# pots.net
KiCad netlist of a schematic drawn in EAGLE
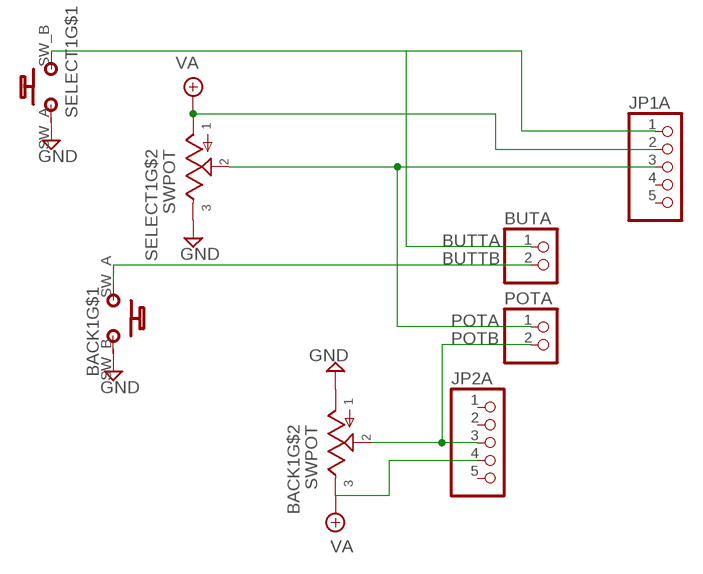
[diagram p0: schematic, sheet 1]

(export (version "E")
  (design (tool "Eeschema 10.0.6"))
  (components
    (comp (ref "BACK1")
      (value "SWPOT")
      (footprint "eagle-import:SWPOT")
      (libsource (lib "eagle-import") (part "SWPOT"))
    )
    (comp (ref "BUTA")
      (value "PINHD-1X2")
      (footprint "eagle-import:1X02")
      (libsource (lib "eagle-import") (part "PINHD-1X2"))
    )
    (comp (ref "JP1A")
      (value "PINHD-1X5")
      (footprint "eagle-import:1X05")
      (libsource (lib "eagle-import") (part "PINHD-1X5"))
    )
    (comp (ref "JP2A")
      (value "PINHD-1X5")
      (footprint "eagle-import:1X05")
      (libsource (lib "eagle-import") (part "PINHD-1X5"))
    )
    (comp (ref "POTA")
      (value "PINHD-1X2")
      (footprint "eagle-import:1X02")
      (libsource (lib "eagle-import") (part "PINHD-1X2"))
    )
    (comp (ref "SELECT1")
      (value "SWPOT")
      (footprint "eagle-import:SWPOT")
      (libsource (lib "eagle-import") (part "SWPOT"))
    )
  )
  (nets
    (net (code "1") (name "/BUTTA") (class "Default")
      (node (ref "BUTA") (pin "1") (pinfunction "1_1") (pintype "passive"))
      (node (ref "JP1A") (pin "1") (pinfunction "1_1") (pintype "passive"))
      (node (ref "SELECT1") (pin "SW_B") (pinfunction "B_B_SW_B") (pintype "passive"))
    )
    (net (code "2") (name "/BUTTB") (class "Default")
      (node (ref "BACK1") (pin "SW_A") (pinfunction "B_A_SW_A") (pintype "passive"))
      (node (ref "BUTA") (pin "2") (pinfunction "2_2") (pintype "passive"))
    )
    (net (code "3") (name "/POTA") (class "Default")
      (node (ref "JP1A") (pin "3") (pinfunction "3_3") (pintype "passive"))
      (node (ref "POTA") (pin "1") (pinfunction "1_1") (pintype "passive"))
      (node (ref "SELECT1") (pin "POT_W") (pinfunction "POT_W_POT_W") (pintype "passive"))
    )
    (net (code "4") (name "/POTB") (class "Default")
      (node (ref "BACK1") (pin "POT_W") (pinfunction "POT_W_POT_W") (pintype "passive"))
      (node (ref "JP2A") (pin "3") (pinfunction "3_3") (pintype "passive"))
      (node (ref "POTA") (pin "2") (pinfunction "2_2") (pintype "passive"))
    )
    (net (code "5") (name "GND") (class "Default")
      (node (ref "BACK1") (pin "POT_B") (pinfunction "POT_B_POT_B") (pintype "passive"))
      (node (ref "BACK1") (pin "SW_B") (pinfunction "B_B_SW_B") (pintype "passive"))
      (node (ref "SELECT1") (pin "POT_A") (pinfunction "POT_A_POT_A") (pintype "passive"))
      (node (ref "SELECT1") (pin "SW_A") (pinfunction "B_A_SW_A") (pintype "passive"))
    )
    (net (code "6") (name "VA") (class "Default")
      (node (ref "BACK1") (pin "POT_A") (pinfunction "POT_A_POT_A") (pintype "passive"))
      (node (ref "JP1A") (pin "2") (pinfunction "2_2") (pintype "passive"))
      (node (ref "JP2A") (pin "4") (pinfunction "4_4") (pintype "passive"))
      (node (ref "SELECT1") (pin "POT_B") (pinfunction "POT_B_POT_B") (pintype "passive"))
    )
    (net (code "7") (name "unconnected-(JP1A-Pad4)") (class "Default")
      (node (ref "JP1A") (pin "4") (pinfunction "4_4") (pintype "passive"))
    )
    (net (code "8") (name "unconnected-(JP1A-Pad5)") (class "Default")
      (node (ref "JP1A") (pin "5") (pinfunction "5_5") (pintype "passive"))
    )
    (net (code "9") (name "unconnected-(JP2A-Pad1)") (class "Default")
      (node (ref "JP2A") (pin "1") (pinfunction "1_1") (pintype "passive"))
    )
    (net (code "10") (name "unconnected-(JP2A-Pad2)") (class "Default")
      (node (ref "JP2A") (pin "2") (pinfunction "2_2") (pintype "passive"))
    )
    (net (code "11") (name "unconnected-(JP2A-Pad5)") (class "Default")
      (node (ref "JP2A") (pin "5") (pinfunction "5_5") (pintype "passive"))
    )
  )
)
